# P07_MICRO_SD_FAN_ARM_JTAG.net
KiCad netlist of a schematic drawn in Altium Designer
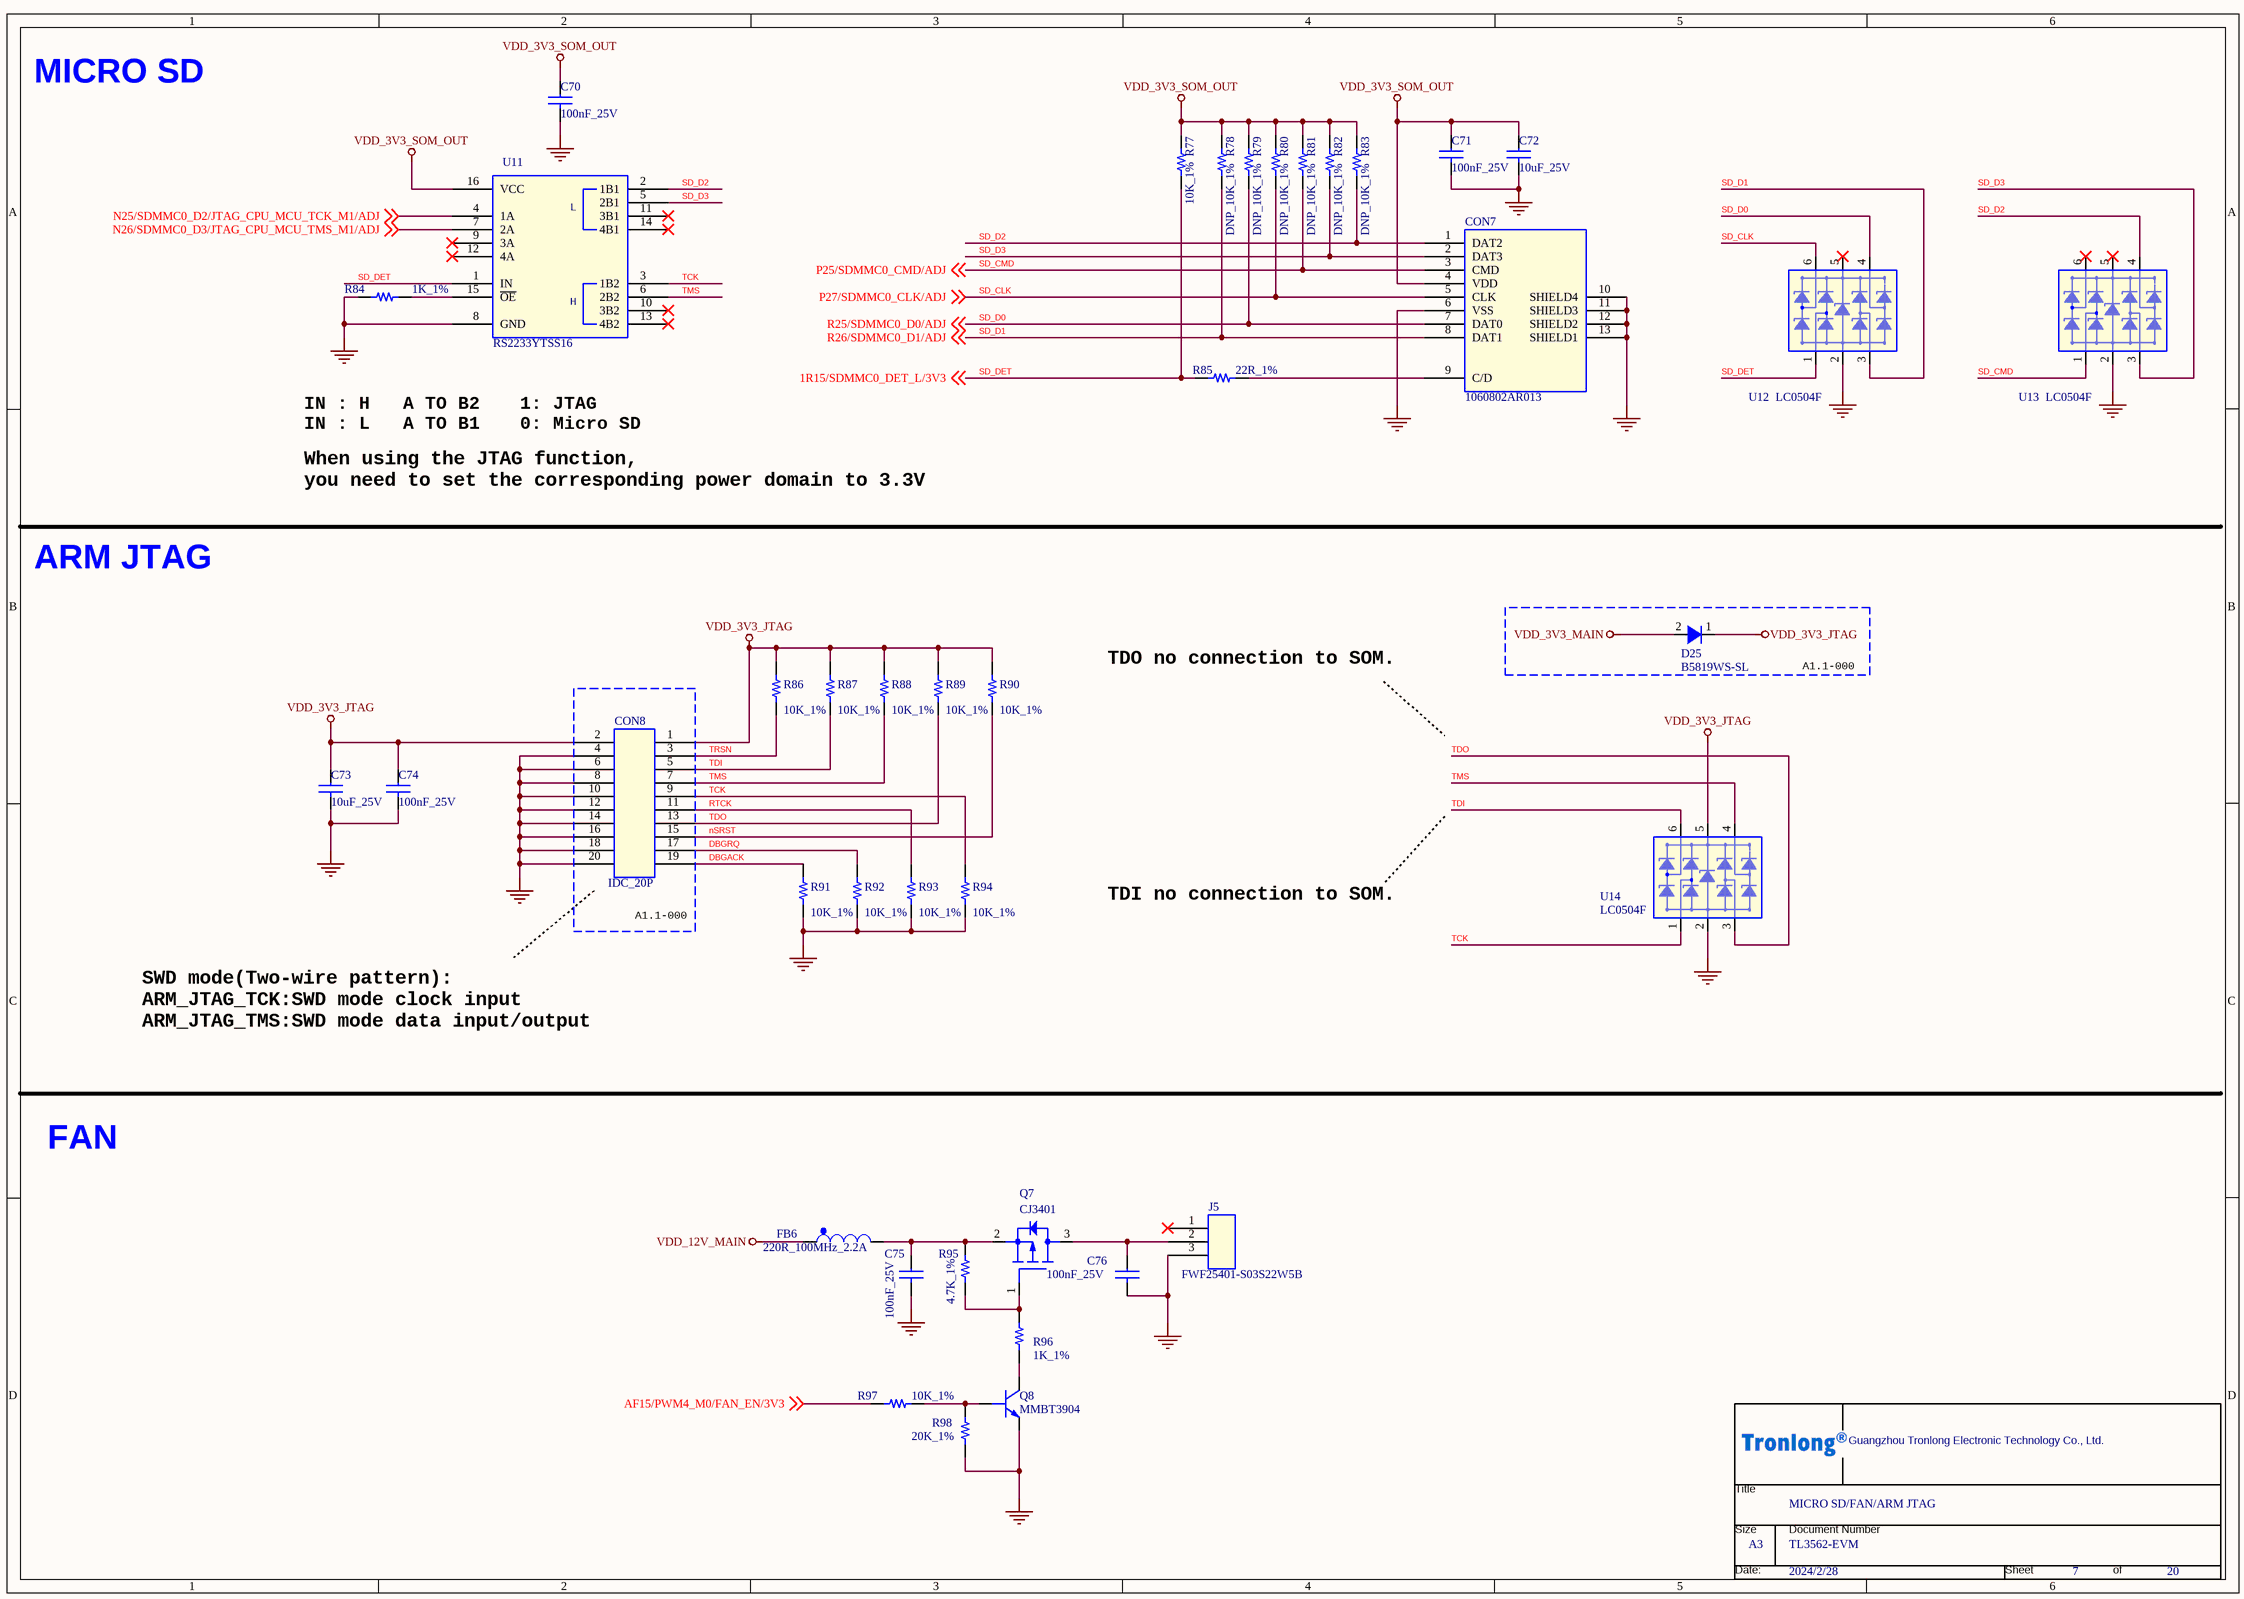
[diagram p0: P07_MICRO SD_FAN_ARM JTAG.SchDoc]

(export (version "E")
  (design (tool "Eeschema 10.0.6"))
  (components
    (comp (ref "C70")
      (value "100nF_25V")
      (footprint "C0402")
      (description "贴片陶瓷电容,100nF,10%,25V,X5R")
      (libsource (lib "*") (part "CAP NP_Dup3"))
    )
    (comp (ref "C71")
      (value "100nF_25V")
      (footprint "C0402")
      (description "贴片陶瓷电容,100nF,10%,25V,X5R")
      (libsource (lib "*") (part "CAP NP_Dup3"))
    )
    (comp (ref "C72")
      (value "10uF_25V")
      (footprint "C0603")
      (description "贴片陶瓷电容,10uF,10%,10V,X5R")
      (libsource (lib "*") (part "CAP NP_Dup3"))
    )
    (comp (ref "C73")
      (value "10uF_25V")
      (footprint "C0603")
      (description "贴片陶瓷电容,10uF,10%,10V,X5R")
      (libsource (lib "*") (part "CAP NP_Dup3"))
    )
    (comp (ref "C74")
      (value "100nF_25V")
      (footprint "C0402")
      (description "贴片陶瓷电容,100nF,10%,25V,X5R")
      (libsource (lib "*") (part "CAP NP_Dup3"))
    )
    (comp (ref "C75")
      (value "100nF_25V")
      (footprint "C0402")
      (description "贴片陶瓷电容,100nF,10%,25V,X5R")
      (libsource (lib "*") (part "CAP NP_Dup3"))
    )
    (comp (ref "C76")
      (value "100nF_25V")
      (footprint "C0402")
      (description "贴片陶瓷电容,100nF,10%,25V,X5R")
      (libsource (lib "*") (part "CAP NP_Dup3"))
    )
    (comp (ref "CON7")
      (value "1060802AR013")
      (footprint "CON_TF_CARD")
      (description "Micro SD卡座,9PIN,90度,贴片，GE- T-FLASH PUSH TYPE外焊式外壳带弹片1.80H(3U)")
      (fields (field (name "MANUFACTURER") "广州高炬电子科技有限公司(TORCH)"))
      (libsource (lib "*") (part "PROCONN SDC009-52-D_3"))
    )
    (comp (ref "CON8")
      (value "IDC_20P")
      (footprint "TL3588-EVM-A1.2-000:con_2d54_2x10_th_box")
      (description "简易牛角座,2X10PIN,间距2.54MM,180度,公座,黑色,插件")
      (fields
        (field (name "MANUFACTURER PARTNUMBER") "FBH25401-D20S1004K6K")
        (field (name "MANUFACTURER") "深圳特思嘉工业电子有限公司（TXGA）")
      )
      (libsource (lib "*") (part "CON20A"))
    )
    (comp (ref "D25")
      (value "B5819WS-SL")
      (footprint "SOD-323")
      (description "肖特基二极管,VR=40V,IF=1A,VF=0.6V@1A")
      (fields (field (name "TIINTPARTNUMBER") "1E0013") (field (name "MFR") "On Semiconductor"))
      (libsource (lib "*") (part "Diode200mA250V_2"))
    )
    (comp (ref "FB6")
      (value "220R_100MHz_2.2A")
      (footprint "L0603")
      (description "磁珠,50mΩ,2.2A,220R@100MHz")
      (fields
        (field (name "MANUFACTURER PARTNUMBER") "UPZ1608U221-2R2TF")
        (field (name "MANUFACTURER") "深圳顺络电子股份有限公司（Sunlord）")
      )
      (libsource (lib "*") (part "FB_0"))
    )
    (comp (ref "J5")
      (value "FWF25401-S03S22W5B")
      (footprint "mol22-23-2031")
      (description "端子座,3PIN,间距2.54MM,180度,2510连接器,白色,插件")
      (fields (field (name "MANUFACTURER") "深圳特思嘉工业电子有限公司（TXGA）"))
      (libsource (lib "*") (part "CON3"))
    )
    (comp (ref "Q7")
      (value "CJ3401")
      (footprint "SOT23-3")
      (description "MOSFET,P沟道,VDSS=-30V,VGSS=±12V,ID=-4.2A,PD=0.35W,VGS(th)=-1.3V")
      (fields (field (name "MANUFACTURER") "江苏长晶科技有限公司（JSCJ）"))
      (libsource (lib "*") (part "MOSFET P SOT"))
    )
    (comp (ref "Q8")
      (value "MMBT3904")
      (footprint "SOT23-3_DBZ3")
      (description "BJT,NPN,Vceo=40V,Ic=200mA,fT=300MHz,PD=200mW")
      (fields (field (name "MANUFACTURER") "江苏长晶科技有限公司（JSCJ）"))
      (libsource (lib "*") (part "MMBT3904/SOT"))
    )
    (comp (ref "R77")
      (value "10K_1%")
      (footprint "R0402")
      (description "贴片电阻,10K,±1%,1/16W")
      (libsource (lib "*") (part "Resistor_Dup3"))
    )
    (comp (ref "R78")
      (value "DNP_10K_1%")
      (footprint "R0402")
      (description "贴片电阻,10K,±1%,1/16W")
      (libsource (lib "*") (part "Resistor_Dup3"))
    )
    (comp (ref "R79")
      (value "DNP_10K_1%")
      (footprint "R0402")
      (description "贴片电阻,10K,±1%,1/16W")
      (libsource (lib "*") (part "Resistor_Dup3"))
    )
    (comp (ref "R80")
      (value "DNP_10K_1%")
      (footprint "R0402")
      (description "贴片电阻,10K,±1%,1/16W")
      (libsource (lib "*") (part "Resistor_Dup3"))
    )
    (comp (ref "R81")
      (value "DNP_10K_1%")
      (footprint "R0402")
      (description "贴片电阻,10K,±1%,1/16W")
      (libsource (lib "*") (part "Resistor_Dup3"))
    )
    (comp (ref "R82")
      (value "DNP_10K_1%")
      (footprint "R0402")
      (description "贴片电阻,10K,±1%,1/16W")
      (libsource (lib "*") (part "Resistor_Dup3"))
    )
    (comp (ref "R83")
      (value "DNP_10K_1%")
      (footprint "R0402")
      (description "贴片电阻,10K,±1%,1/16W")
      (libsource (lib "*") (part "Resistor_Dup3"))
    )
    (comp (ref "R84")
      (value "1K_1%")
      (footprint "R0402")
      (description "贴片电阻,1K,±1%,1/16W")
      (libsource (lib "*") (part "Resistor_Dup3"))
    )
    (comp (ref "R85")
      (value "22R_1%")
      (footprint "R0402")
      (description "贴片电阻,22R,±1%,1/16W")
      (libsource (lib "*") (part "Resistor_Dup3"))
    )
    (comp (ref "R86")
      (value "10K_1%")
      (footprint "R0402")
      (description "贴片电阻,10K,±1%,1/16W")
      (libsource (lib "*") (part "Resistor_Dup3"))
    )
    (comp (ref "R87")
      (value "10K_1%")
      (footprint "R0402")
      (description "贴片电阻,10K,±1%,1/16W")
      (libsource (lib "*") (part "Resistor_Dup3"))
    )
    (comp (ref "R88")
      (value "10K_1%")
      (footprint "R0402")
      (description "贴片电阻,10K,±1%,1/16W")
      (libsource (lib "*") (part "Resistor_Dup3"))
    )
    (comp (ref "R89")
      (value "10K_1%")
      (footprint "R0402")
      (description "贴片电阻,10K,±1%,1/16W")
      (libsource (lib "*") (part "Resistor_Dup3"))
    )
    (comp (ref "R90")
      (value "10K_1%")
      (footprint "R0402")
      (description "贴片电阻,10K,±1%,1/16W")
      (libsource (lib "*") (part "Resistor_Dup3"))
    )
    (comp (ref "R91")
      (value "10K_1%")
      (footprint "R0402")
      (description "贴片电阻,10K,±1%,1/16W")
      (libsource (lib "*") (part "Resistor_Dup3"))
    )
    (comp (ref "R92")
      (value "10K_1%")
      (footprint "R0402")
      (description "贴片电阻,10K,±1%,1/16W")
      (libsource (lib "*") (part "Resistor_Dup3"))
    )
    (comp (ref "R93")
      (value "10K_1%")
      (footprint "R0402")
      (description "贴片电阻,10K,±1%,1/16W")
      (libsource (lib "*") (part "Resistor_Dup3"))
    )
    (comp (ref "R94")
      (value "10K_1%")
      (footprint "R0402")
      (description "贴片电阻,10K,±1%,1/16W")
      (libsource (lib "*") (part "Resistor_Dup3"))
    )
    (comp (ref "R95")
      (value "4.7K_1%")
      (footprint "R0402")
      (description "贴片电阻,4.7K,±1%,1/16W")
      (fields
        (field (name "MISTRAL PART NO") "110009031036-R")
        (field (name "MFR_PART_NUMBER") "ERJ-2RNF6981V")
      )
      (libsource (lib "*") (part "Resistor_Dup3"))
    )
    (comp (ref "R96")
      (value "1K_1%")
      (footprint "R0402")
      (description "贴片电阻,1K,±1%,1/16W")
      (fields (field (name "DISTRIBUTOR_PART_NUMBER") "NA") (field (name "TOLERANCE") "1%"))
      (libsource (lib "*") (part "Resistor_Dup3"))
    )
    (comp (ref "R97")
      (value "10K_1%")
      (footprint "R0402")
      (description "贴片电阻,10K,±1%,1/16W")
      (fields
        (field (name "MISTRAL PART NO") "110009031036-R")
        (field (name "MFR_PART_NUMBER") "ERJ-2RNF6981V")
      )
      (libsource (lib "*") (part "Resistor_Dup3"))
    )
    (comp (ref "R98")
      (value "20K_1%")
      (footprint "R0402")
      (description "贴片电阻,20K,±1%,1/16W")
      (fields (field (name "DISTRIBUTOR_PART_NUMBER") "NA") (field (name "TOLERANCE") "1%"))
      (libsource (lib "*") (part "Resistor_Dup3"))
    )
    (comp (ref "U11")
      (value "RS2233YTSS16")
      (footprint "TSSOP16")
      (description "4路模拟开关芯片")
      (fields (field (name "MANUFACTURER") "江苏润石科技有限公司（RUNIC）"))
      (libsource (lib "*") (part "TS3A5018DR_2"))
    )
    (comp (ref "U12")
      (value "LC0504F")
      (footprint "SOT363")
      (description "ESD二极管,VRWM=5V,VBR=6V,四组,单向,8KV,15KV")
      (fields
        (field (name "MANUFACTURER") "上海雷卯电子科技有限公司（Leiditech）")
        (field (name "MANUFACTURER PART NUMBER") "PRTR5V0U4Y")
      )
      (libsource (lib "*") (part "PRTR5V0U4Y_0"))
    )
    (comp (ref "U13")
      (value "LC0504F")
      (footprint "SOT363")
      (description "ESD二极管,VRWM=5V,VBR=6V,四组,单向,8KV,15KV")
      (fields
        (field (name "MANUFACTURER") "上海雷卯电子科技有限公司（Leiditech）")
        (field (name "MANUFACTURER PART NUMBER") "PRTR5V0U4Y")
      )
      (libsource (lib "*") (part "PRTR5V0U4Y_0"))
    )
    (comp (ref "U14")
      (value "LC0504F")
      (footprint "SOT363")
      (description "ESD二极管,VRWM=5V,VBR=6V,四组,单向,8KV,15KV")
      (fields
        (field (name "MANUFACTURER") "上海雷卯电子科技有限公司（Leiditech）")
        (field (name "MANUFACTURER PART NUMBER") "PRTR5V0U4Y")
      )
      (libsource (lib "*") (part "PRTR5V0U4Y_0"))
    )
  )
  (nets
    (net (code "1") (name "/DBGACK") (class "Default")
      (node (ref "CON8") (pin "19") (pinfunction "19_19") (pintype "passive"))
      (node (ref "R91") (pin "1") (pinfunction "1_1") (pintype "passive"))
    )
    (net (code "2") (name "/DBGRQ") (class "Default")
      (node (ref "CON8") (pin "17") (pinfunction "17_17") (pintype "passive"))
      (node (ref "R92") (pin "1") (pinfunction "1_1") (pintype "passive"))
    )
    (net (code "3") (name "/RTCK") (class "Default")
      (node (ref "CON8") (pin "11") (pinfunction "11_11") (pintype "passive"))
      (node (ref "R93") (pin "1") (pinfunction "1_1") (pintype "passive"))
    )
    (net (code "4") (name "/SD_D2") (class "Default")
      (node (ref "CON7") (pin "1") (pinfunction "DAT2_1") (pintype "passive"))
      (node (ref "R83") (pin "2") (pinfunction "2_2") (pintype "passive"))
      (node (ref "U11") (pin "2") (pinfunction "1B1_2") (pintype "passive"))
      (node (ref "U13") (pin "4") (pinfunction "4_4") (pintype "passive"))
    )
    (net (code "5") (name "/SD_D3") (class "Default")
      (node (ref "CON7") (pin "2") (pinfunction "DAT3_2") (pintype "passive"))
      (node (ref "R82") (pin "2") (pinfunction "2_2") (pintype "passive"))
      (node (ref "U11") (pin "5") (pinfunction "2B1_5") (pintype "passive"))
      (node (ref "U13") (pin "3") (pinfunction "3_3") (pintype "passive"))
    )
    (net (code "6") (name "/TCK") (class "Default")
      (node (ref "CON8") (pin "9") (pinfunction "9_9") (pintype "passive"))
      (node (ref "R94") (pin "1") (pinfunction "1_1") (pintype "passive"))
      (node (ref "U11") (pin "3") (pinfunction "1B2_3") (pintype "passive"))
      (node (ref "U14") (pin "1") (pinfunction "1_1") (pintype "passive"))
    )
    (net (code "7") (name "/TDI") (class "Default")
      (node (ref "CON8") (pin "5") (pinfunction "5_5") (pintype "passive"))
      (node (ref "R87") (pin "2") (pinfunction "2_2") (pintype "passive"))
      (node (ref "U14") (pin "6") (pinfunction "6_6") (pintype "passive"))
    )
    (net (code "8") (name "/TDO") (class "Default")
      (node (ref "CON8") (pin "13") (pinfunction "13_13") (pintype "passive"))
      (node (ref "R89") (pin "2") (pinfunction "2_2") (pintype "passive"))
      (node (ref "U14") (pin "3") (pinfunction "3_3") (pintype "passive"))
    )
    (net (code "9") (name "/TMS") (class "Default")
      (node (ref "CON8") (pin "7") (pinfunction "7_7") (pintype "passive"))
      (node (ref "R88") (pin "2") (pinfunction "2_2") (pintype "passive"))
      (node (ref "U11") (pin "6") (pinfunction "2B2_6") (pintype "passive"))
      (node (ref "U14") (pin "4") (pinfunction "4_4") (pintype "passive"))
    )
    (net (code "10") (name "/TRSN") (class "Default")
      (node (ref "CON8") (pin "3") (pinfunction "3_3") (pintype "passive"))
      (node (ref "R86") (pin "2") (pinfunction "2_2") (pintype "passive"))
    )
    (net (code "11") (name "/nSRST") (class "Default")
      (node (ref "CON8") (pin "15") (pinfunction "15_15") (pintype "passive"))
      (node (ref "R90") (pin "2") (pinfunction "2_2") (pintype "passive"))
    )
    (net (code "12") (name "1R15{slash}SDMMC0_DET_L{slash}3V3") (class "Default")
      (node (ref "R77") (pin "2") (pinfunction "2_2") (pintype "passive"))
      (node (ref "R85") (pin "1") (pinfunction "1_1") (pintype "passive"))
      (node (ref "U11") (pin "1") (pinfunction "IN_1") (pintype "passive"))
      (node (ref "U12") (pin "1") (pinfunction "1_1") (pintype "passive"))
    )
    (net (code "13") (name "AF15{slash}PWM4_M0{slash}FAN_EN{slash}3V3") (class "Default")
      (node (ref "R97") (pin "1") (pinfunction "1_1") (pintype "passive"))
    )
    (net (code "14") (name "GND") (class "Default")
      (node (ref "C70") (pin "2") (pinfunction "2_2") (pintype "passive"))
      (node (ref "C71") (pin "2") (pinfunction "2_2") (pintype "passive"))
      (node (ref "C72") (pin "2") (pinfunction "2_2") (pintype "passive"))
      (node (ref "C73") (pin "2") (pinfunction "2_2") (pintype "passive"))
      (node (ref "C74") (pin "2") (pinfunction "2_2") (pintype "passive"))
      (node (ref "C75") (pin "2") (pinfunction "2_2") (pintype "passive"))
      (node (ref "C76") (pin "2") (pinfunction "2_2") (pintype "passive"))
      (node (ref "CON7") (pin "10") (pinfunction "SHIELD4_10") (pintype "power_in"))
      (node (ref "CON7") (pin "11") (pinfunction "SHIELD3_11") (pintype "passive"))
      (node (ref "CON7") (pin "12") (pinfunction "SHIELD2_12") (pintype "passive"))
      (node (ref "CON7") (pin "13") (pinfunction "SHIELD1_13") (pintype "passive"))
      (node (ref "CON7") (pin "6") (pinfunction "VSS_6") (pintype "power_in"))
      (node (ref "CON8") (pin "10") (pinfunction "10_10") (pintype "passive"))
      (node (ref "CON8") (pin "12") (pinfunction "12_12") (pintype "passive"))
      (node (ref "CON8") (pin "14") (pinfunction "14_14") (pintype "passive"))
      (node (ref "CON8") (pin "16") (pinfunction "16_16") (pintype "passive"))
      (node (ref "CON8") (pin "18") (pinfunction "18_18") (pintype "passive"))
      (node (ref "CON8") (pin "20") (pinfunction "20_20") (pintype "passive"))
      (node (ref "CON8") (pin "4") (pinfunction "4_4") (pintype "passive"))
      (node (ref "CON8") (pin "6") (pinfunction "6_6") (pintype "passive"))
      (node (ref "CON8") (pin "8") (pinfunction "8_8") (pintype "passive"))
      (node (ref "J5") (pin "3") (pinfunction "3_3") (pintype "passive"))
      (node (ref "Q8") (pin "2") (pinfunction "E_2") (pintype "passive"))
      (node (ref "R84") (pin "2") (pinfunction "2_2") (pintype "passive"))
      (node (ref "R91") (pin "2") (pinfunction "2_2") (pintype "passive"))
      (node (ref "R92") (pin "2") (pinfunction "2_2") (pintype "passive"))
      (node (ref "R93") (pin "2") (pinfunction "2_2") (pintype "passive"))
      (node (ref "R94") (pin "2") (pinfunction "2_2") (pintype "passive"))
      (node (ref "R98") (pin "2") (pinfunction "2_2") (pintype "passive"))
      (node (ref "U11") (pin "8") (pinfunction "GND_8") (pintype "power_in"))
      (node (ref "U12") (pin "2") (pinfunction "2_2") (pintype "passive"))
      (node (ref "U13") (pin "2") (pinfunction "2_2") (pintype "passive"))
      (node (ref "U14") (pin "2") (pinfunction "2_2") (pintype "passive"))
    )
    (net (code "15") (name "N25{slash}SDMMC0_D2{slash}JTAG_CPU_MCU_TCK_M1{slash}ADJ") (class "Default")
      (node (ref "U11") (pin "4") (pinfunction "1A_4") (pintype "passive"))
    )
    (net (code "16") (name "N26{slash}SDMMC0_D3{slash}JTAG_CPU_MCU_TMS_M1{slash}ADJ") (class "Default")
      (node (ref "U11") (pin "7") (pinfunction "2A_7") (pintype "passive"))
    )
    (net (code "17") (name "Net-(CON7-C{slash}D)") (class "Default")
      (node (ref "CON7") (pin "9") (pinfunction "C/D_9") (pintype "passive"))
      (node (ref "R85") (pin "2") (pinfunction "2_2") (pintype "passive"))
    )
    (net (code "18") (name "Net-(Q7-DRAIN)") (class "Default")
      (node (ref "C76") (pin "1") (pinfunction "1_1") (pintype "passive"))
      (node (ref "J5") (pin "2") (pinfunction "2_2") (pintype "passive"))
      (node (ref "Q7") (pin "3") (pinfunction "DRAIN_3") (pintype "passive"))
    )
    (net (code "19") (name "Net-(Q7-GATE)") (class "Default")
      (node (ref "Q7") (pin "1") (pinfunction "GATE_1") (pintype "passive"))
      (node (ref "R95") (pin "2") (pinfunction "2_2") (pintype "passive"))
      (node (ref "R96") (pin "1") (pinfunction "1_1") (pintype "passive"))
    )
    (net (code "20") (name "Net-(Q7-SOURCE)") (class "Default")
      (node (ref "C75") (pin "1") (pinfunction "1_1") (pintype "passive"))
      (node (ref "FB6") (pin "2") (pinfunction "2_2") (pintype "passive"))
      (node (ref "Q7") (pin "2") (pinfunction "SOURCE_2") (pintype "passive"))
      (node (ref "R95") (pin "1") (pinfunction "1_1") (pintype "passive"))
    )
    (net (code "21") (name "Net-(Q8-B)") (class "Default")
      (node (ref "Q8") (pin "1") (pinfunction "B_1") (pintype "passive"))
      (node (ref "R97") (pin "2") (pinfunction "2_2") (pintype "passive"))
      (node (ref "R98") (pin "1") (pinfunction "1_1") (pintype "passive"))
    )
    (net (code "22") (name "Net-(Q8-C)") (class "Default")
      (node (ref "Q8") (pin "3") (pinfunction "C_3") (pintype "passive"))
      (node (ref "R96") (pin "2") (pinfunction "2_2") (pintype "passive"))
    )
    (net (code "23") (name "Net-(U11-~{OE})") (class "Default")
      (node (ref "R84") (pin "1") (pinfunction "1_1") (pintype "passive"))
      (node (ref "U11") (pin "15") (pinfunction "~{OE}_15") (pintype "passive"))
    )
    (net (code "24") (name "P25{slash}SDMMC0_CMD{slash}ADJ") (class "Default")
      (node (ref "CON7") (pin "3") (pinfunction "CMD_3") (pintype "passive"))
      (node (ref "R81") (pin "2") (pinfunction "2_2") (pintype "passive"))
      (node (ref "U13") (pin "1") (pinfunction "1_1") (pintype "passive"))
    )
    (net (code "25") (name "P27{slash}SDMMC0_CLK{slash}ADJ") (class "Default")
      (node (ref "CON7") (pin "5") (pinfunction "CLK_5") (pintype "passive"))
      (node (ref "R80") (pin "2") (pinfunction "2_2") (pintype "passive"))
      (node (ref "U12") (pin "6") (pinfunction "6_6") (pintype "passive"))
    )
    (net (code "26") (name "R25{slash}SDMMC0_D0{slash}ADJ") (class "Default")
      (node (ref "CON7") (pin "7") (pinfunction "DAT0_7") (pintype "passive"))
      (node (ref "R79") (pin "2") (pinfunction "2_2") (pintype "passive"))
      (node (ref "U12") (pin "4") (pinfunction "4_4") (pintype "passive"))
    )
    (net (code "27") (name "R26{slash}SDMMC0_D1{slash}ADJ") (class "Default")
      (node (ref "CON7") (pin "8") (pinfunction "DAT1_8") (pintype "passive"))
      (node (ref "R78") (pin "2") (pinfunction "2_2") (pintype "passive"))
      (node (ref "U12") (pin "3") (pinfunction "3_3") (pintype "passive"))
    )
    (net (code "28") (name "VDD_3V3_JTAG") (class "Default")
      (node (ref "C73") (pin "1") (pinfunction "1_1") (pintype "passive"))
      (node (ref "C74") (pin "1") (pinfunction "1_1") (pintype "passive"))
      (node (ref "CON8") (pin "1") (pinfunction "1_1") (pintype "passive"))
      (node (ref "CON8") (pin "2") (pinfunction "2_2") (pintype "passive"))
      (node (ref "D25") (pin "1") (pinfunction "Anode_1") (pintype "passive"))
      (node (ref "R86") (pin "1") (pinfunction "1_1") (pintype "passive"))
      (node (ref "R87") (pin "1") (pinfunction "1_1") (pintype "passive"))
      (node (ref "R88") (pin "1") (pinfunction "1_1") (pintype "passive"))
      (node (ref "R89") (pin "1") (pinfunction "1_1") (pintype "passive"))
      (node (ref "R90") (pin "1") (pinfunction "1_1") (pintype "passive"))
      (node (ref "U14") (pin "5") (pinfunction "5_5") (pintype "passive"))
    )
    (net (code "29") (name "VDD_3V3_MAIN") (class "Default")
      (node (ref "D25") (pin "2") (pinfunction "Cathode_2") (pintype "passive"))
    )
    (net (code "30") (name "VDD_3V3_SOM_OUT") (class "Default")
      (node (ref "C70") (pin "1") (pinfunction "1_1") (pintype "passive"))
      (node (ref "C71") (pin "1") (pinfunction "1_1") (pintype "passive"))
      (node (ref "C72") (pin "1") (pinfunction "1_1") (pintype "passive"))
      (node (ref "CON7") (pin "4") (pinfunction "VDD_4") (pintype "power_in"))
      (node (ref "R77") (pin "1") (pinfunction "1_1") (pintype "passive"))
      (node (ref "R78") (pin "1") (pinfunction "1_1") (pintype "passive"))
      (node (ref "R79") (pin "1") (pinfunction "1_1") (pintype "passive"))
      (node (ref "R80") (pin "1") (pinfunction "1_1") (pintype "passive"))
      (node (ref "R81") (pin "1") (pinfunction "1_1") (pintype "passive"))
      (node (ref "R82") (pin "1") (pinfunction "1_1") (pintype "passive"))
      (node (ref "R83") (pin "1") (pinfunction "1_1") (pintype "passive"))
      (node (ref "U11") (pin "16") (pinfunction "VCC_16") (pintype "power_in"))
    )
    (net (code "31") (name "VDD_12V_MAIN") (class "Default")
      (node (ref "FB6") (pin "1") (pinfunction "1_1") (pintype "passive"))
    )
    (net (code "32") (name "unconnected-(J5-Pad1)") (class "Default")
      (node (ref "J5") (pin "1") (pinfunction "1_1") (pintype "passive+no_connect"))
    )
    (net (code "33") (name "unconnected-(U11-3A-Pad9)") (class "Default")
      (node (ref "U11") (pin "9") (pinfunction "3A_9") (pintype "passive+no_connect"))
    )
    (net (code "34") (name "unconnected-(U11-3B1-Pad11)") (class "Default")
      (node (ref "U11") (pin "11") (pinfunction "3B1_11") (pintype "passive+no_connect"))
    )
    (net (code "35") (name "unconnected-(U11-3B2-Pad10)") (class "Default")
      (node (ref "U11") (pin "10") (pinfunction "3B2_10") (pintype "passive+no_connect"))
    )
    (net (code "36") (name "unconnected-(U11-4A-Pad12)") (class "Default")
      (node (ref "U11") (pin "12") (pinfunction "4A_12") (pintype "passive+no_connect"))
    )
    (net (code "37") (name "unconnected-(U11-4B1-Pad14)") (class "Default")
      (node (ref "U11") (pin "14") (pinfunction "4B1_14") (pintype "passive+no_connect"))
    )
    (net (code "38") (name "unconnected-(U11-4B2-Pad13)") (class "Default")
      (node (ref "U11") (pin "13") (pinfunction "4B2_13") (pintype "passive+no_connect"))
    )
    (net (code "39") (name "unconnected-(U12-Pad5)") (class "Default")
      (node (ref "U12") (pin "5") (pinfunction "5_5") (pintype "passive+no_connect"))
    )
    (net (code "40") (name "unconnected-(U13-Pad5)") (class "Default")
      (node (ref "U13") (pin "5") (pinfunction "5_5") (pintype "passive+no_connect"))
    )
    (net (code "41") (name "unconnected-(U13-Pad6)") (class "Default")
      (node (ref "U13") (pin "6") (pinfunction "6_6") (pintype "passive+no_connect"))
    )
  )
)
